# PushButtonBlue.net
KiCad netlist of a schematic drawn in Altium Designer
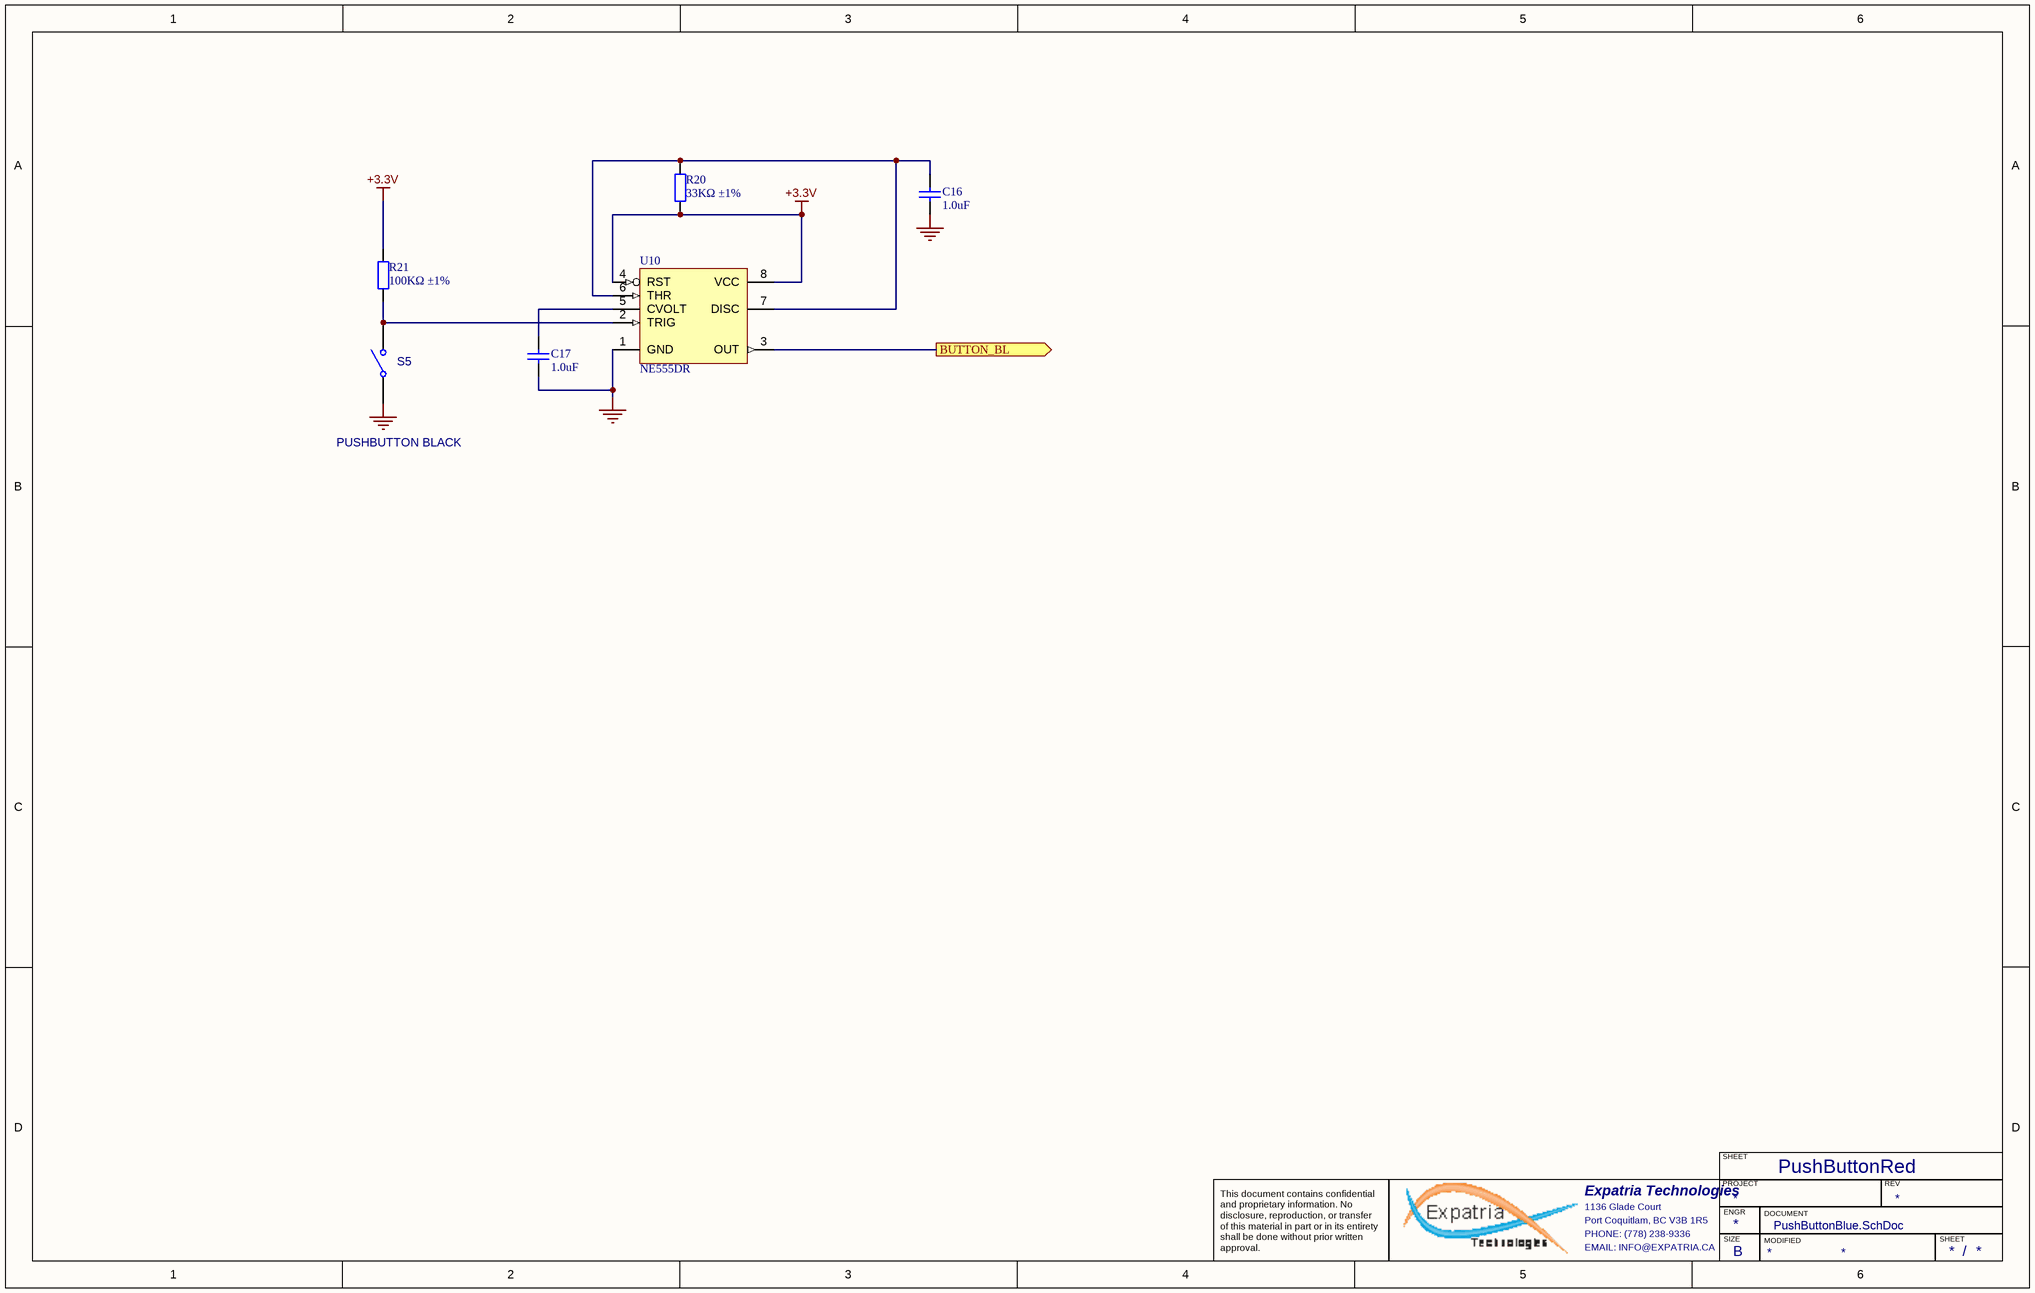
[diagram p0: PushButtonBlue.SchDoc]

(export (version "E")
  (design (tool "Eeschema 10.0.6"))
  (components
    (comp (ref "C16")
      (value "1.0uF")
      (footprint "0402_C")
      (description "Chip capacitor")
      (fields
        (field (name "MANUFACTURER") "Samsung Electro-Mechanics")
        (field (name "PARTNUMBER") "CL05A105KA5NQNC")
      )
      (libsource (lib "Cap") (part "0402 1.0uF (105) 10% 25V"))
    )
    (comp (ref "C17")
      (value "1.0uF")
      (footprint "0402_C")
      (description "Chip capacitor")
      (fields
        (field (name "MANUFACTURER") "Samsung Electro-Mechanics")
        (field (name "PARTNUMBER") "CL05A105KA5NQNC")
      )
      (libsource (lib "Cap") (part "0402 1.0uF (105) 10% 25V"))
    )
    (comp (ref "R20")
      (value "33KΩ ±1%")
      (footprint "0402_R")
      (description "Chip resistor")
      (fields (field (name "MANUFACTURER") "Uniroyal Elec") (field (name "PARTNUMBER") "0402WGF3302TCE"))
      (libsource (lib "RES") (part "0402 33K (3302) 1%"))
    )
    (comp (ref "R21")
      (value "100KΩ ±1%")
      (footprint "0402_R")
      (description "Chip resistor")
      (fields (field (name "MANUFACTURER") "Uniroyal Elec") (field (name "PARTNUMBER") "0402WGF1003TCE"))
      (libsource (lib "RES") (part "0402 100K (1003) 1%"))
    )
    (comp (ref "S5")
      (value "PUSHBUTTON BLACK")
      (footprint "D6C10F1LFS_BLUE")
      (description "SWITCH PUSH SPST-NO 0.1A 32V RED")
      (libsource (lib "bluebell") (part "D6R40 F1 LFS"))
    )
    (comp (ref "U10")
      (value "NE555DR")
      (footprint "SOIC-8_150mil")
      (description "时基集成")
      (libsource (lib "IC") (part "NE555DR_[C7593]"))
    )
  )
  (nets
    (net (code "1") (name "+3.3V") (class "Default")
      (node (ref "R20") (pin "1") (pinfunction "1_1") (pintype "passive"))
      (node (ref "R21") (pin "2") (pinfunction "2_2") (pintype "passive"))
      (node (ref "U10") (pin "4") (pinfunction "RST_4") (pintype "input"))
      (node (ref "U10") (pin "8") (pinfunction "VCC_8") (pintype "power_in"))
    )
    (net (code "2") (name "/BUTTON_BL") (class "Default")
      (node (ref "U10") (pin "3") (pinfunction "OUT_3") (pintype "output"))
    )
    (net (code "3") (name "GND") (class "Default")
      (node (ref "C16") (pin "1") (pinfunction "1_1") (pintype "passive"))
      (node (ref "C17") (pin "2") (pinfunction "2_2") (pintype "passive"))
      (node (ref "S5") (pin "1") (pinfunction "COMMON_1") (pintype "passive"))
      (node (ref "U10") (pin "1") (pinfunction "GND_1") (pintype "power_in"))
    )
    (net (code "4") (name "Net-(S5-NO)") (class "Default")
      (node (ref "R21") (pin "1") (pinfunction "1_1") (pintype "passive"))
      (node (ref "S5") (pin "2") (pinfunction "NO_2") (pintype "passive"))
      (node (ref "U10") (pin "2") (pinfunction "TRIG_2") (pintype "input"))
    )
    (net (code "5") (name "Net-(U10-CVOLT)") (class "Default")
      (node (ref "C17") (pin "1") (pinfunction "1_1") (pintype "passive"))
      (node (ref "U10") (pin "5") (pinfunction "CVOLT_5") (pintype "passive"))
    )
    (net (code "6") (name "Net-(U10-DISC)") (class "Default")
      (node (ref "C16") (pin "2") (pinfunction "2_2") (pintype "passive"))
      (node (ref "R20") (pin "2") (pinfunction "2_2") (pintype "passive"))
      (node (ref "U10") (pin "6") (pinfunction "THR_6") (pintype "input"))
      (node (ref "U10") (pin "7") (pinfunction "DISC_7") (pintype "open_collector"))
    )
  )
)
